# Esquemarico.net
KiCad netlist of a schematic drawn in Altium Designer
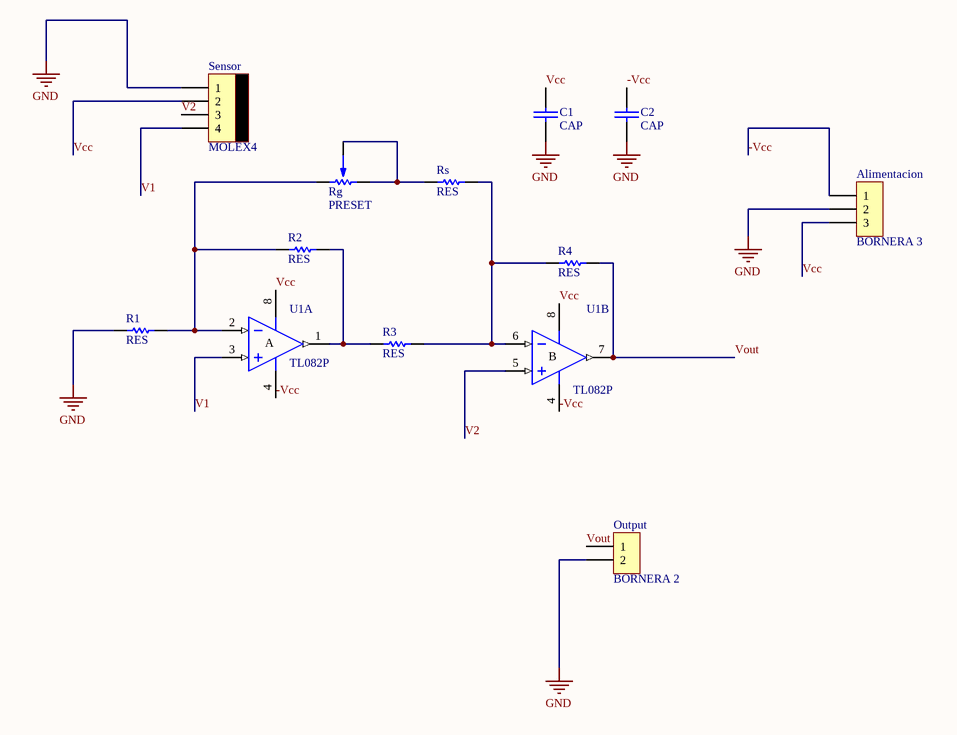
[diagram p0: Esquemarico.SchDoc]

(export (version "E")
  (design (tool "Eeschema 10.0.6"))
  (components
    (comp (ref "Alimentacion")
      (value "BORNERA 3")
      (footprint "BORNERA3")
      (libsource (lib "LIBEBAL") (part "BORNERA 3"))
    )
    (comp (ref "C1") (value "CAP") (footprint "CAP100") (libsource (lib "LIBEBAL") (part "CAP")))
    (comp (ref "C2") (value "CAP") (footprint "CAP100") (libsource (lib "LIBEBAL") (part "CAP")))
    (comp (ref "Output")
      (value "BORNERA 2")
      (footprint "BORNERA2")
      (libsource (lib "LIBEBAL") (part "BORNERA 2"))
    )
    (comp (ref "R1") (value "RES") (footprint "0805") (libsource (lib "LIBEBAL") (part "RES")))
    (comp (ref "R2") (value "RES") (footprint "0805") (libsource (lib "LIBEBAL") (part "RES")))
    (comp (ref "R3") (value "RES") (footprint "0805") (libsource (lib "LIBEBAL") (part "RES")))
    (comp (ref "R4") (value "RES") (footprint "0805") (libsource (lib "LIBEBAL") (part "RES")))
    (comp (ref "Rg") (value "PRESET") (footprint "PRESET V") (libsource (lib "LIBEBAL") (part "PRESET")))
    (comp (ref "Rs") (value "RES") (footprint "0805") (libsource (lib "LIBEBAL") (part "RES")))
    (comp (ref "Sensor") (value "MOLEX4") (footprint "MOLEX4") (libsource (lib "LIBEBAL") (part "MOLEX4")))
    (comp (ref "U1")
      (value "TL082P")
      (footprint "P008")
      (description "JFET-Input Operational Amplifier")
      (fields (field (name "PUBLISHER") "Altium Limited"))
      (libsource (lib "TI Operational Amplifier") (part "TL082P"))
    )
  )
  (nets
    (net (code "1") (name "/-Vcc") (class "Default")
      (node (ref "Alimentacion") (pin "1") (pinfunction "1_1") (pintype "passive"))
      (node (ref "C2") (pin "1") (pinfunction "1_1") (pintype "passive"))
      (node (ref "U1") (pin "4") (pinfunction "V-_4") (pintype "power_in"))
    )
    (net (code "2") (name "/V1") (class "Default")
      (node (ref "Sensor") (pin "4") (pinfunction "4_4") (pintype "passive"))
      (node (ref "U1") (pin "3") (pinfunction "IN+_3") (pintype "input"))
    )
    (net (code "3") (name "/V2") (class "Default")
      (node (ref "Sensor") (pin "3") (pinfunction "3_3") (pintype "passive"))
      (node (ref "U1") (pin "5") (pinfunction "IN+_5") (pintype "input"))
    )
    (net (code "4") (name "/Vcc") (class "Default")
      (node (ref "Alimentacion") (pin "3") (pinfunction "3_3") (pintype "passive"))
      (node (ref "C1") (pin "1") (pinfunction "1_1") (pintype "passive"))
      (node (ref "Sensor") (pin "2") (pinfunction "2_2") (pintype "passive"))
      (node (ref "U1") (pin "8") (pinfunction "V+_8") (pintype "power_in"))
    )
    (net (code "5") (name "/Vout") (class "Default")
      (node (ref "Output") (pin "1") (pinfunction "1_1") (pintype "passive"))
      (node (ref "R4") (pin "2") (pinfunction "2_2") (pintype "passive"))
      (node (ref "U1") (pin "7") (pinfunction "OUT_7") (pintype "output"))
    )
    (net (code "6") (name "GND") (class "Default")
      (node (ref "Alimentacion") (pin "2") (pinfunction "2_2") (pintype "passive"))
      (node (ref "C1") (pin "2") (pinfunction "2_2") (pintype "passive"))
      (node (ref "C2") (pin "2") (pinfunction "2_2") (pintype "passive"))
      (node (ref "Output") (pin "2") (pinfunction "2_2") (pintype "passive"))
      (node (ref "R1") (pin "1") (pinfunction "1_1") (pintype "passive"))
      (node (ref "Sensor") (pin "1") (pinfunction "1_1") (pintype "passive"))
    )
    (net (code "7") (name "Net-(Rg-Pad2)") (class "Default")
      (node (ref "Rg") (pin "2") (pinfunction "2_2") (pintype "passive"))
      (node (ref "Rg") (pin "3") (pinfunction "3_3") (pintype "passive"))
      (node (ref "Rs") (pin "1") (pinfunction "1_1") (pintype "passive"))
    )
    (net (code "8") (name "Net-(U1A-IN-)") (class "Default")
      (node (ref "R1") (pin "2") (pinfunction "2_2") (pintype "passive"))
      (node (ref "R2") (pin "1") (pinfunction "1_1") (pintype "passive"))
      (node (ref "Rg") (pin "1") (pinfunction "1_1") (pintype "passive"))
      (node (ref "U1") (pin "2") (pinfunction "IN-_2") (pintype "input"))
    )
    (net (code "9") (name "Net-(U1A-OUT)") (class "Default")
      (node (ref "R2") (pin "2") (pinfunction "2_2") (pintype "passive"))
      (node (ref "R3") (pin "1") (pinfunction "1_1") (pintype "passive"))
      (node (ref "U1") (pin "1") (pinfunction "OUT_1") (pintype "output"))
    )
    (net (code "10") (name "Net-(U1B-IN-)") (class "Default")
      (node (ref "R3") (pin "2") (pinfunction "2_2") (pintype "passive"))
      (node (ref "R4") (pin "1") (pinfunction "1_1") (pintype "passive"))
      (node (ref "Rs") (pin "2") (pinfunction "2_2") (pintype "passive"))
      (node (ref "U1") (pin "6") (pinfunction "IN-_6") (pintype "input"))
    )
  )
)
